# komparator.net
KiCad netlist of a schematic drawn in EAGLE
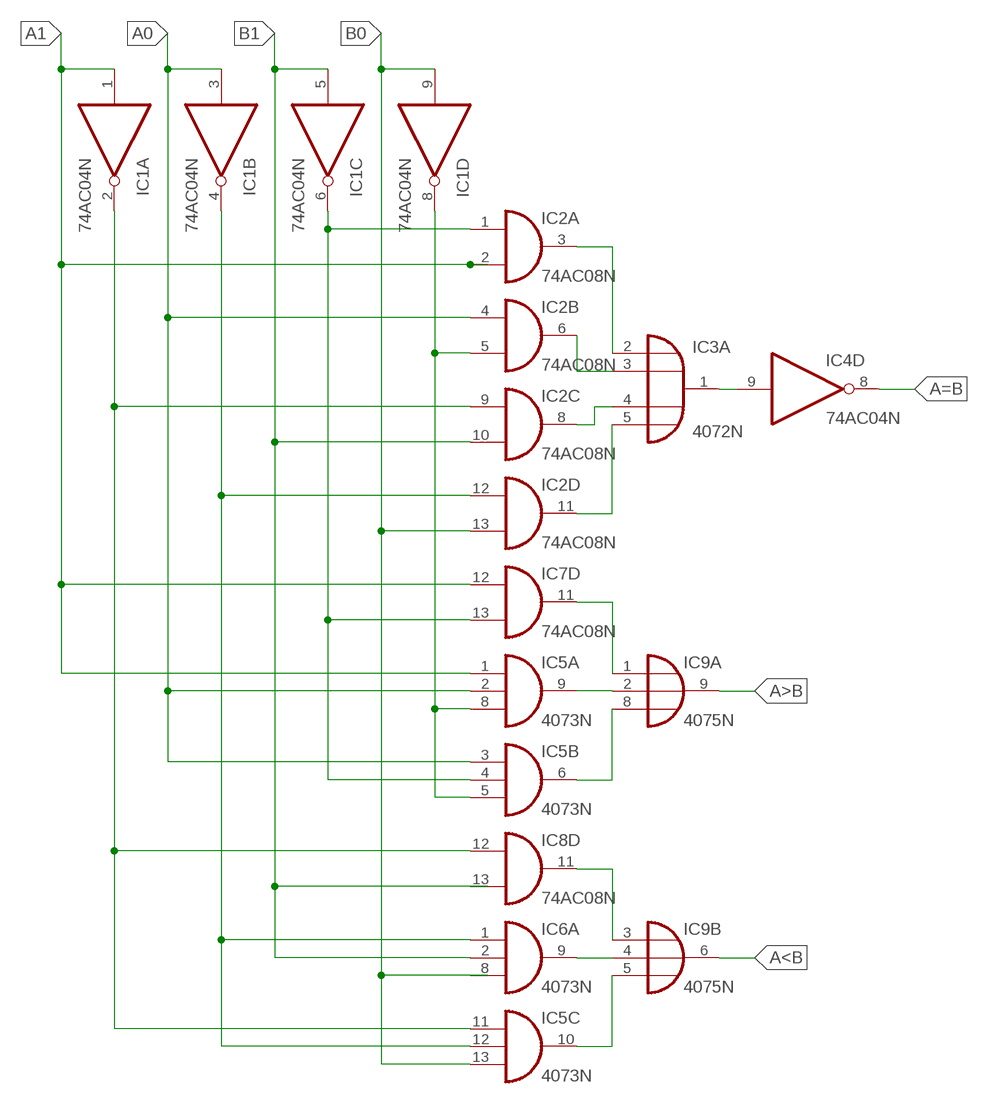
[diagram p0: schematic, sheet 1]

(export (version "E")
  (design (tool "Eeschema 10.0.6"))
  (components
    (comp (ref "IC1")
      (value "74AC04N")
      (footprint "eagle-import:DIL14")
      (libsource (lib "eagle-import") (part "7404NAC"))
    )
    (comp (ref "IC2")
      (value "74AC08N")
      (footprint "eagle-import:DIL14")
      (libsource (lib "eagle-import") (part "7408NAC"))
    )
    (comp (ref "IC3")
      (value "4072N")
      (footprint "eagle-import:DIL14")
      (libsource (lib "eagle-import") (part "4072N"))
    )
    (comp (ref "IC4")
      (value "74AC04N")
      (footprint "eagle-import:DIL14")
      (libsource (lib "eagle-import") (part "7404NAC"))
    )
    (comp (ref "IC5")
      (value "4073N")
      (footprint "eagle-import:DIL14")
      (libsource (lib "eagle-import") (part "4073N"))
    )
    (comp (ref "IC6")
      (value "4073N")
      (footprint "eagle-import:DIL14")
      (libsource (lib "eagle-import") (part "4073N"))
    )
    (comp (ref "IC7")
      (value "74AC08N")
      (footprint "eagle-import:DIL14")
      (libsource (lib "eagle-import") (part "7408NAC"))
    )
    (comp (ref "IC8")
      (value "74AC08N")
      (footprint "eagle-import:DIL14")
      (libsource (lib "eagle-import") (part "7408NAC"))
    )
    (comp (ref "IC9")
      (value "4075N")
      (footprint "eagle-import:DIL14")
      (libsource (lib "eagle-import") (part "4075N"))
    )
  )
  (nets
    (net (code "1") (name "A0") (class "Default")
      (node (ref "IC1") (pin "3") (pinfunction "I_3") (pintype "input"))
      (node (ref "IC2") (pin "4") (pinfunction "I0_4") (pintype "input"))
      (node (ref "IC5") (pin "2") (pinfunction "I1_2") (pintype "input"))
      (node (ref "IC5") (pin "3") (pinfunction "I0_3") (pintype "input"))
    )
    (net (code "2") (name "A1") (class "Default")
      (node (ref "IC1") (pin "1") (pinfunction "I_1") (pintype "input"))
      (node (ref "IC2") (pin "2") (pinfunction "I1_2") (pintype "input"))
      (node (ref "IC5") (pin "1") (pinfunction "I0_1") (pintype "input"))
      (node (ref "IC7") (pin "12") (pinfunction "I0_12") (pintype "input"))
    )
    (net (code "3") (name "A<B") (class "Default")
      (node (ref "IC9") (pin "6") (pinfunction "O_6") (pintype "output"))
    )
    (net (code "4") (name "A=B") (class "Default")
      (node (ref "IC4") (pin "8") (pinfunction "O_8") (pintype "output"))
    )
    (net (code "5") (name "A>B") (class "Default")
      (node (ref "IC9") (pin "9") (pinfunction "O_9") (pintype "output"))
    )
    (net (code "6") (name "B0") (class "Default")
      (node (ref "IC1") (pin "9") (pinfunction "I_9") (pintype "input"))
      (node (ref "IC2") (pin "13") (pinfunction "I1_13") (pintype "input"))
      (node (ref "IC5") (pin "13") (pinfunction "I2_13") (pintype "input"))
    )
    (net (code "7") (name "B1") (class "Default")
      (node (ref "IC1") (pin "5") (pinfunction "I_5") (pintype "input"))
      (node (ref "IC2") (pin "10") (pinfunction "I1_10") (pintype "input"))
      (node (ref "IC6") (pin "2") (pinfunction "I1_2") (pintype "input"))
    )
    (net (code "8") (name "Net-(IC1A-O)") (class "Default")
      (node (ref "IC1") (pin "2") (pinfunction "O_2") (pintype "output"))
      (node (ref "IC2") (pin "9") (pinfunction "I0_9") (pintype "input"))
      (node (ref "IC5") (pin "11") (pinfunction "I0_11") (pintype "input"))
      (node (ref "IC8") (pin "12") (pinfunction "I0_12") (pintype "input"))
    )
    (net (code "9") (name "Net-(IC1B-O)") (class "Default")
      (node (ref "IC1") (pin "4") (pinfunction "O_4") (pintype "output"))
      (node (ref "IC2") (pin "12") (pinfunction "I0_12") (pintype "input"))
      (node (ref "IC5") (pin "12") (pinfunction "I1_12") (pintype "input"))
      (node (ref "IC6") (pin "1") (pinfunction "I0_1") (pintype "input"))
    )
    (net (code "10") (name "Net-(IC1C-O)") (class "Default")
      (node (ref "IC1") (pin "6") (pinfunction "O_6") (pintype "output"))
      (node (ref "IC2") (pin "1") (pinfunction "I0_1") (pintype "input"))
      (node (ref "IC5") (pin "4") (pinfunction "I1_4") (pintype "input"))
      (node (ref "IC7") (pin "13") (pinfunction "I1_13") (pintype "input"))
    )
    (net (code "11") (name "Net-(IC1D-O)") (class "Default")
      (node (ref "IC1") (pin "8") (pinfunction "O_8") (pintype "output"))
      (node (ref "IC2") (pin "5") (pinfunction "I1_5") (pintype "input"))
      (node (ref "IC5") (pin "5") (pinfunction "I2_5") (pintype "input"))
      (node (ref "IC5") (pin "8") (pinfunction "I2_8") (pintype "input"))
    )
    (net (code "12") (name "Net-(IC2A-O)") (class "Default")
      (node (ref "IC2") (pin "3") (pinfunction "O_3") (pintype "output"))
      (node (ref "IC3") (pin "2") (pinfunction "I0_2") (pintype "input"))
    )
    (net (code "13") (name "Net-(IC2B-O)") (class "Default")
      (node (ref "IC2") (pin "6") (pinfunction "O_6") (pintype "output"))
      (node (ref "IC3") (pin "3") (pinfunction "I1_3") (pintype "input"))
    )
    (net (code "14") (name "Net-(IC2C-O)") (class "Default")
      (node (ref "IC2") (pin "8") (pinfunction "O_8") (pintype "output"))
      (node (ref "IC3") (pin "4") (pinfunction "I2_4") (pintype "input"))
    )
    (net (code "15") (name "Net-(IC2D-O)") (class "Default")
      (node (ref "IC2") (pin "11") (pinfunction "O_11") (pintype "output"))
      (node (ref "IC3") (pin "5") (pinfunction "I3_5") (pintype "input"))
    )
    (net (code "16") (name "Net-(IC3A-O)") (class "Default")
      (node (ref "IC3") (pin "1") (pinfunction "O_1") (pintype "output"))
      (node (ref "IC4") (pin "9") (pinfunction "I_9") (pintype "input"))
    )
    (net (code "17") (name "Net-(IC5A-O)") (class "Default")
      (node (ref "IC5") (pin "9") (pinfunction "O_9") (pintype "output"))
      (node (ref "IC9") (pin "2") (pinfunction "I1_2") (pintype "input"))
    )
    (net (code "18") (name "Net-(IC5B-O)") (class "Default")
      (node (ref "IC5") (pin "6") (pinfunction "O_6") (pintype "output"))
      (node (ref "IC9") (pin "8") (pinfunction "I2_8") (pintype "input"))
    )
    (net (code "19") (name "Net-(IC5C-O)") (class "Default")
      (node (ref "IC5") (pin "10") (pinfunction "O_10") (pintype "output"))
      (node (ref "IC9") (pin "5") (pinfunction "I2_5") (pintype "input"))
    )
    (net (code "20") (name "Net-(IC6A-O)") (class "Default")
      (node (ref "IC6") (pin "9") (pinfunction "O_9") (pintype "output"))
      (node (ref "IC9") (pin "4") (pinfunction "I1_4") (pintype "input"))
    )
    (net (code "21") (name "Net-(IC7D-O)") (class "Default")
      (node (ref "IC7") (pin "11") (pinfunction "O_11") (pintype "output"))
      (node (ref "IC9") (pin "1") (pinfunction "I0_1") (pintype "input"))
    )
    (net (code "22") (name "Net-(IC8D-O)") (class "Default")
      (node (ref "IC8") (pin "11") (pinfunction "O_11") (pintype "output"))
      (node (ref "IC9") (pin "3") (pinfunction "I0_3") (pintype "input"))
    )
    (net (code "23") (name "unconnected-(IC6A-I2-Pad8)") (class "Default")
      (node (ref "IC6") (pin "8") (pinfunction "I2_8") (pintype "input"))
    )
    (net (code "24") (name "unconnected-(IC8D-I1-Pad13)") (class "Default")
      (node (ref "IC8") (pin "13") (pinfunction "I1_13") (pintype "input"))
    )
  )
)
